# SCH_TempMate_2.net
KiCad netlist of a schematic drawn in EasyEDA
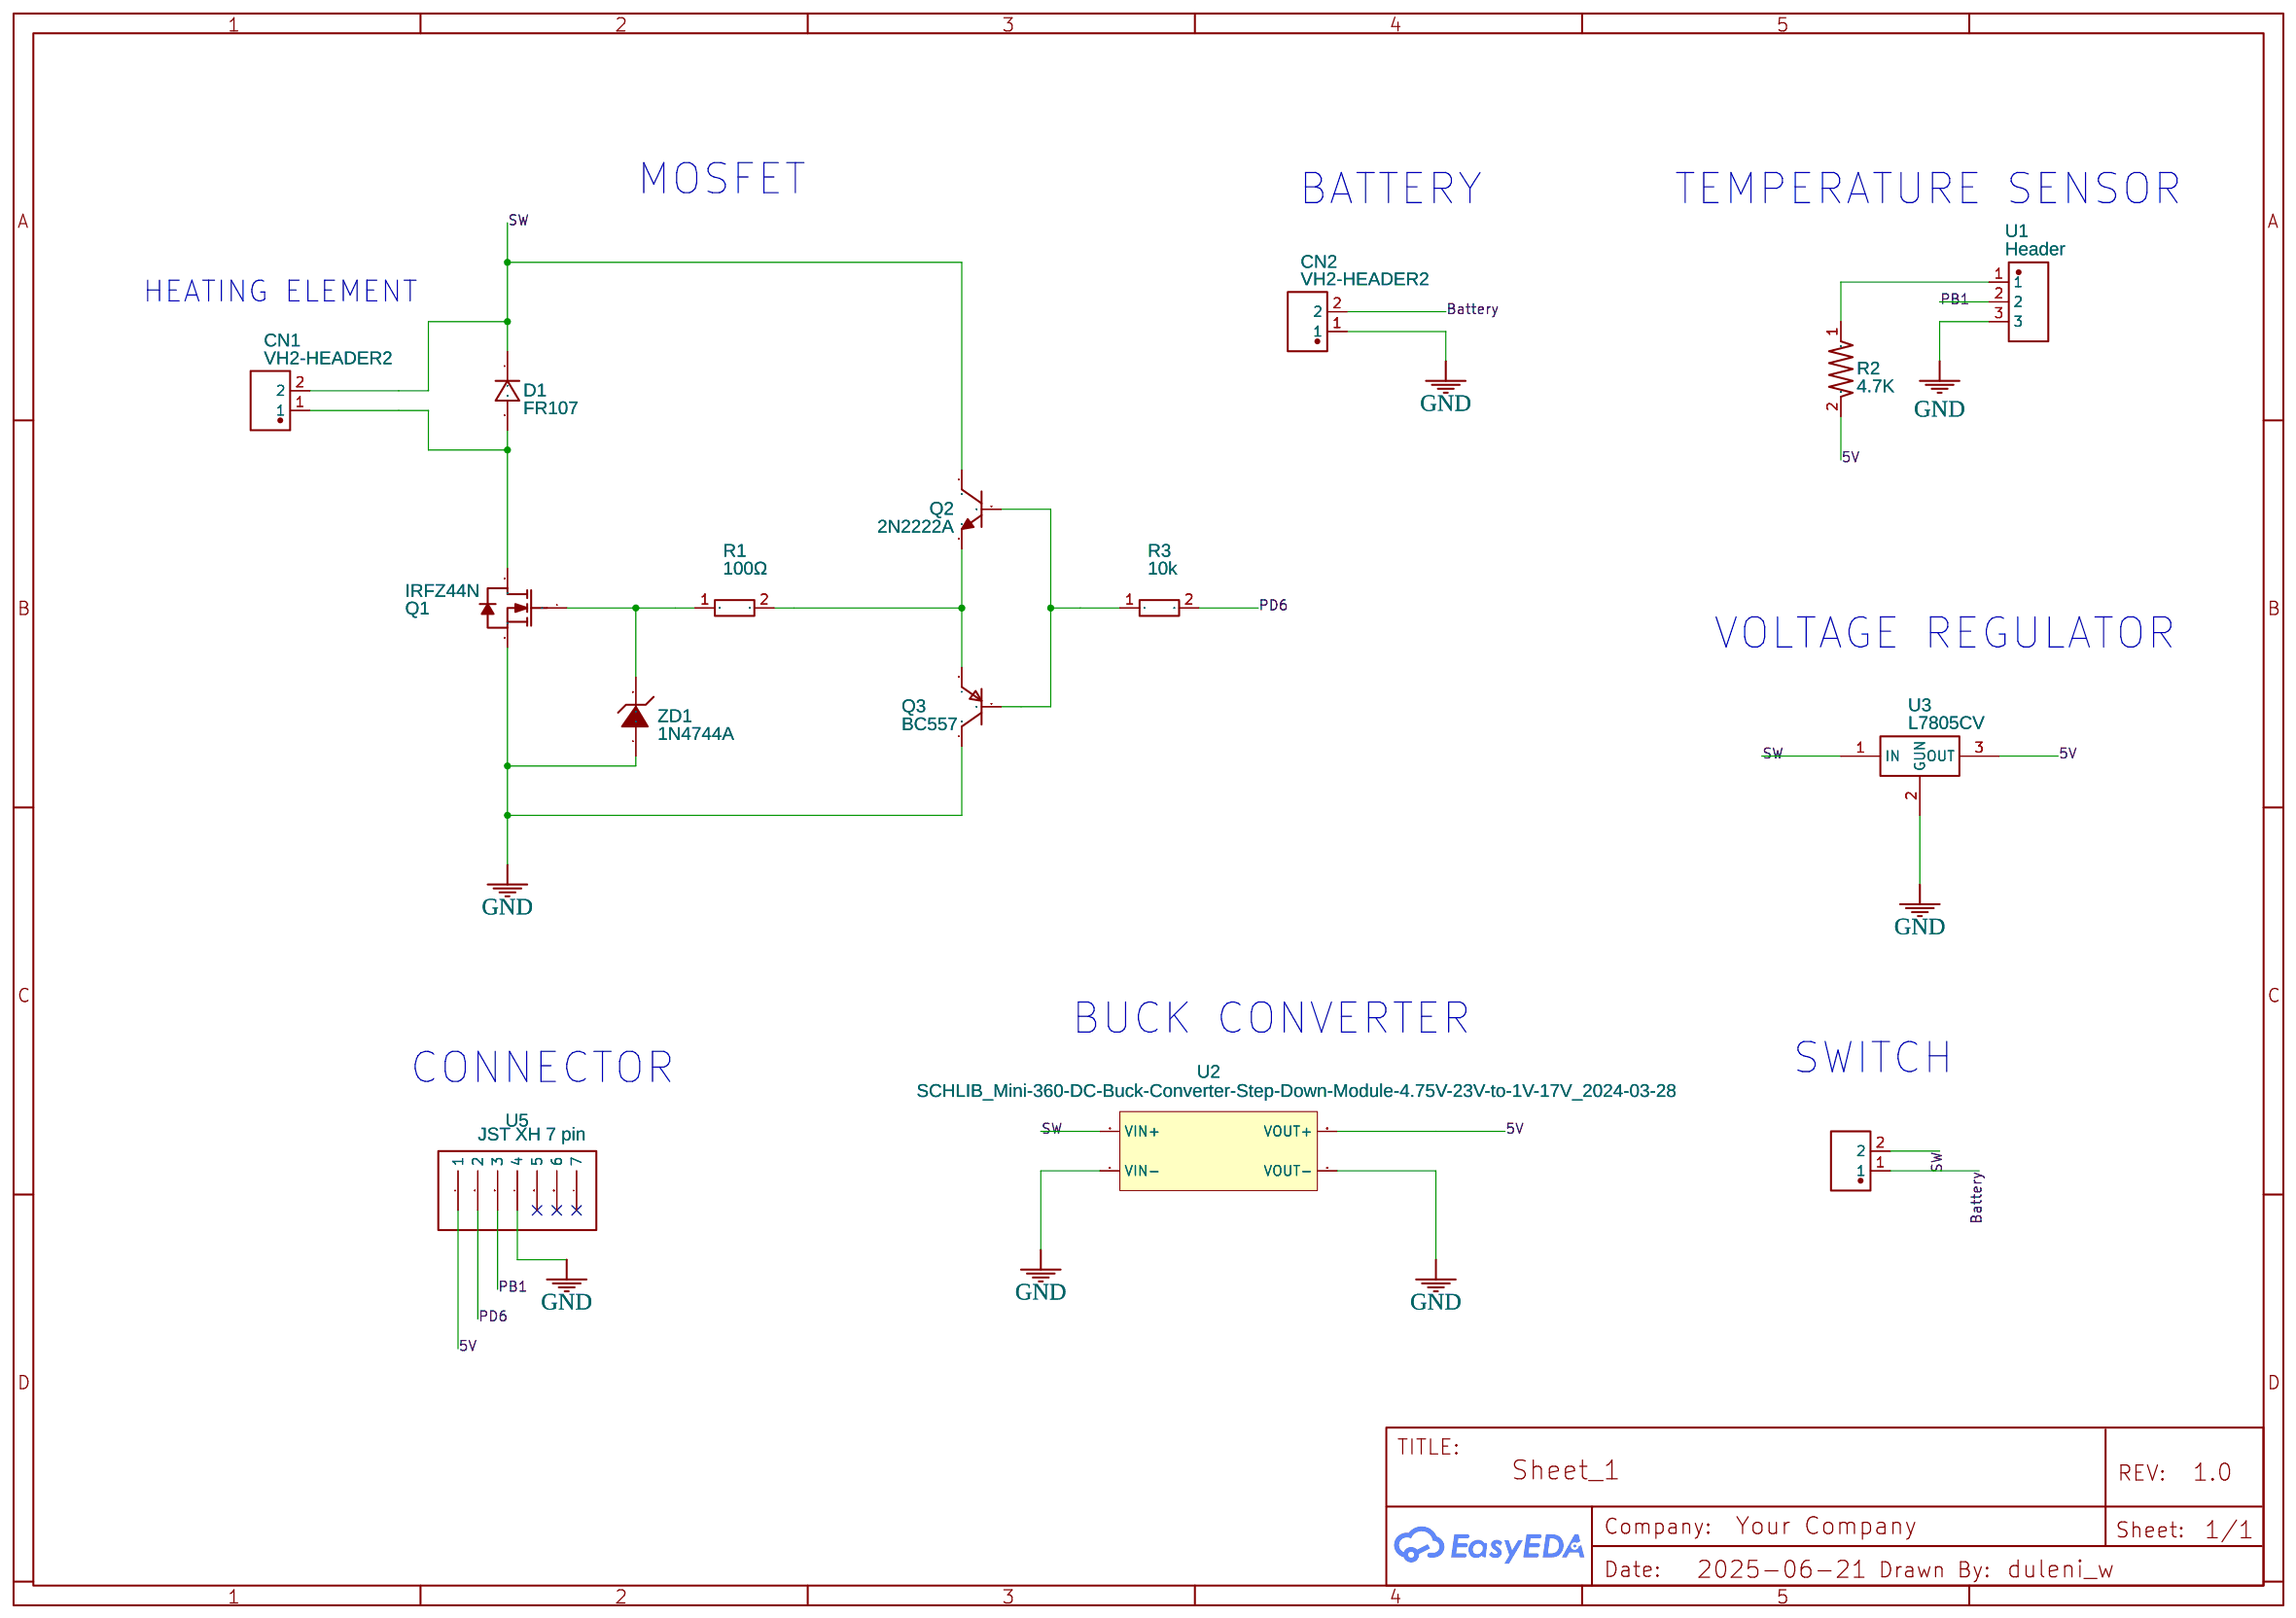
[diagram p0: schematic sheet]

(export (version "E")
  (design (tool "Eeschema 10.0.6"))
  (components
    (comp (ref "CN1")
      (value "VH2-HEADER2")
      (fields (field (name "Manufacturer Part") "VH2-Header2"))
      (libsource (lib "") (part "VH2-HEADER2"))
    )
    (comp (ref "CN2")
      (value "VH2-HEADER2")
      (fields (field (name "Manufacturer Part") "VH2-Header2"))
      (libsource (lib "") (part "VH2-HEADER2"))
    )
    (comp (ref "CN3")
      (value "VH2-HEADER2")
      (fields (field (name "Manufacturer Part") "VH2-Header2"))
      (libsource (lib "") (part "VH2-HEADER2"))
    )
    (comp (ref "D1") (value "FR107") (libsource (lib "") (part "Through Hole Diode")))
    (comp (ref "Q1")
      (value "IRFZ44N")
      (fields (field (name "Manufacturer") "minos(迈诺斯)"))
      (libsource (lib "") (part "IRFZ44N"))
    )
    (comp (ref "Q2")
      (value "2N2222A")
      (fields (field (name "Manufacturer") "BLUE ROCKET(蓝箭)"))
      (libsource (lib "") (part "2N2222A"))
    )
    (comp (ref "Q3")
      (value "BC557")
      (fields
        (field (name "Manufacturer Part") "BC557(RANGE:420-800)")
        (field (name "Manufacturer") "CJ(江苏长电/长晶)")
      )
      (libsource (lib "") (part "BC557"))
    )
    (comp (ref "R1")
      (value "100Ω")
      (fields (field (name "Manufacturer Part") "MF1/4W-330Ω±1% T") (field (name "Manufacturer") "CCO(千志电子)"))
      (libsource (lib "") (part "XOHM-THROUGH-HOLE-RESISTORS-5%-1/4W-D2.3-L6.5MM"))
    )
    (comp (ref "R2") (value "4.7K") (libsource (lib "") (part "res")))
    (comp (ref "R3")
      (value "10k")
      (fields (field (name "Manufacturer Part") "MF1/4W-330Ω±1% T") (field (name "Manufacturer") "CCO(千志电子)"))
      (libsource (lib "") (part "XOHM-THROUGH-HOLE-RESISTORS-5%-1/4W-D2.3-L6.5MM"))
    )
    (comp (ref "U1")
      (value "Header")
      (fields (field (name "Manufacturer Part") "D21122000060-Header3"))
      (libsource (lib "") (part "D21122000060-HEADER3"))
    )
    (comp (ref "U2")
      (value "SCHLIB_Mini-360-DC-Buck-Converter-Step-Down-Module-4.75V-23V-to-1V-17V_2024-03-28")
      (libsource (lib "") (part "SCHLIB_Mini-360-DC-Buck-Converter-Step-Down-Module-4.75V-23V-to-1V-17V_2024-03-28"))
    )
    (comp (ref "U3") (value "L7805CV") (libsource (lib "") (part "L7805CV")))
    (comp (ref "U5") (value "JST XH 7 pin") (libsource (lib "") (part "JST XH 7 pin")))
    (comp (ref "ZD1")
      (value "1N4744A")
      (fields (field (name "Manufacturer") "ST(先科)"))
      (libsource (lib "") (part "1N4744A"))
    )
  )
  (nets
    (net (code "1") (name "/5V") (class "Default")
      (node (ref "R2") (pin "2") (pinfunction "2_2") (pintype "unspecified"))
      (node (ref "U2") (pin "VOUT+") (pinfunction "VOUT+_VOUT+") (pintype "unspecified"))
      (node (ref "U3") (pin "3") (pinfunction "OUT_3") (pintype "unspecified"))
      (node (ref "U5") (pin "1") (pinfunction "1_1") (pintype "unspecified"))
    )
    (net (code "2") (name "/Battery") (class "Default")
      (node (ref "CN2") (pin "2") (pinfunction "2_2") (pintype "unspecified"))
      (node (ref "CN3") (pin "1") (pinfunction "1_1") (pintype "unspecified"))
    )
    (net (code "3") (name "/PB1") (class "Default")
      (node (ref "U1") (pin "2") (pinfunction "2_2") (pintype "unspecified"))
      (node (ref "U5") (pin "3") (pinfunction "3_3") (pintype "unspecified"))
    )
    (net (code "4") (name "/PD6") (class "Default")
      (node (ref "R3") (pin "2") (pinfunction "2_2") (pintype "unspecified"))
      (node (ref "U5") (pin "2") (pinfunction "2_2") (pintype "unspecified"))
    )
    (net (code "5") (name "/SW") (class "Default")
      (node (ref "CN1") (pin "2") (pinfunction "2_2") (pintype "unspecified"))
      (node (ref "CN3") (pin "2") (pinfunction "2_2") (pintype "unspecified"))
      (node (ref "D1") (pin "1") (pinfunction "1_1") (pintype "unspecified"))
      (node (ref "Q2") (pin "1") (pinfunction "C_1") (pintype "unspecified"))
      (node (ref "U2") (pin "VIN+") (pinfunction "VIN+_VIN+") (pintype "unspecified"))
      (node (ref "U3") (pin "1") (pinfunction "IN_1") (pintype "unspecified"))
    )
    (net (code "6") (name "GND") (class "Default")
      (node (ref "CN2") (pin "1") (pinfunction "1_1") (pintype "unspecified"))
      (node (ref "Q1") (pin "3") (pinfunction "S_3") (pintype "unspecified"))
      (node (ref "Q3") (pin "1") (pinfunction "C_1") (pintype "unspecified"))
      (node (ref "U1") (pin "3") (pinfunction "3_3") (pintype "unspecified"))
      (node (ref "U2") (pin "VIN-") (pinfunction "VIN-_VIN-") (pintype "unspecified"))
      (node (ref "U2") (pin "VOUT-") (pinfunction "VOUT-_VOUT-") (pintype "unspecified"))
      (node (ref "U3") (pin "2") (pinfunction "GUN_2") (pintype "unspecified"))
      (node (ref "U5") (pin "4") (pinfunction "4_4") (pintype "unspecified"))
      (node (ref "ZD1") (pin "1") (pinfunction "A_1") (pintype "unspecified"))
    )
    (net (code "7") (name "Net-(Q1-D)") (class "Default")
      (node (ref "CN1") (pin "1") (pinfunction "1_1") (pintype "unspecified"))
      (node (ref "D1") (pin "2") (pinfunction "2_2") (pintype "unspecified"))
      (node (ref "Q1") (pin "2") (pinfunction "D_2") (pintype "unspecified"))
    )
    (net (code "8") (name "Net-(Q1-G)") (class "Default")
      (node (ref "Q1") (pin "1") (pinfunction "G_1") (pintype "unspecified"))
      (node (ref "R1") (pin "1") (pinfunction "1_1") (pintype "unspecified"))
      (node (ref "ZD1") (pin "2") (pinfunction "K_2") (pintype "unspecified"))
    )
    (net (code "9") (name "Net-(Q2-B)") (class "Default")
      (node (ref "Q2") (pin "2") (pinfunction "B_2") (pintype "unspecified"))
      (node (ref "Q3") (pin "2") (pinfunction "B_2") (pintype "unspecified"))
      (node (ref "R3") (pin "1") (pinfunction "1_1") (pintype "unspecified"))
    )
    (net (code "10") (name "Net-(Q2-E)") (class "Default")
      (node (ref "Q2") (pin "3") (pinfunction "E_3") (pintype "unspecified"))
      (node (ref "Q3") (pin "3") (pinfunction "E_3") (pintype "unspecified"))
      (node (ref "R1") (pin "2") (pinfunction "2_2") (pintype "unspecified"))
    )
    (net (code "11") (name "Net-(R2-Pad1)") (class "Default")
      (node (ref "R2") (pin "1") (pinfunction "1_1") (pintype "unspecified"))
      (node (ref "U1") (pin "1") (pinfunction "1_1") (pintype "unspecified"))
    )
    (net (code "12") (name "unconnected-(U5-Pad5)") (class "Default")
      (node (ref "U5") (pin "5") (pinfunction "5_5") (pintype "unspecified+no_connect"))
    )
    (net (code "13") (name "unconnected-(U5-Pad6)") (class "Default")
      (node (ref "U5") (pin "6") (pinfunction "6_6") (pintype "unspecified+no_connect"))
    )
    (net (code "14") (name "unconnected-(U5-Pad7)") (class "Default")
      (node (ref "U5") (pin "7") (pinfunction "7_7") (pintype "unspecified+no_connect"))
    )
  )
)
